# motor-shield01.net
KiCad netlist of a schematic drawn in EAGLE
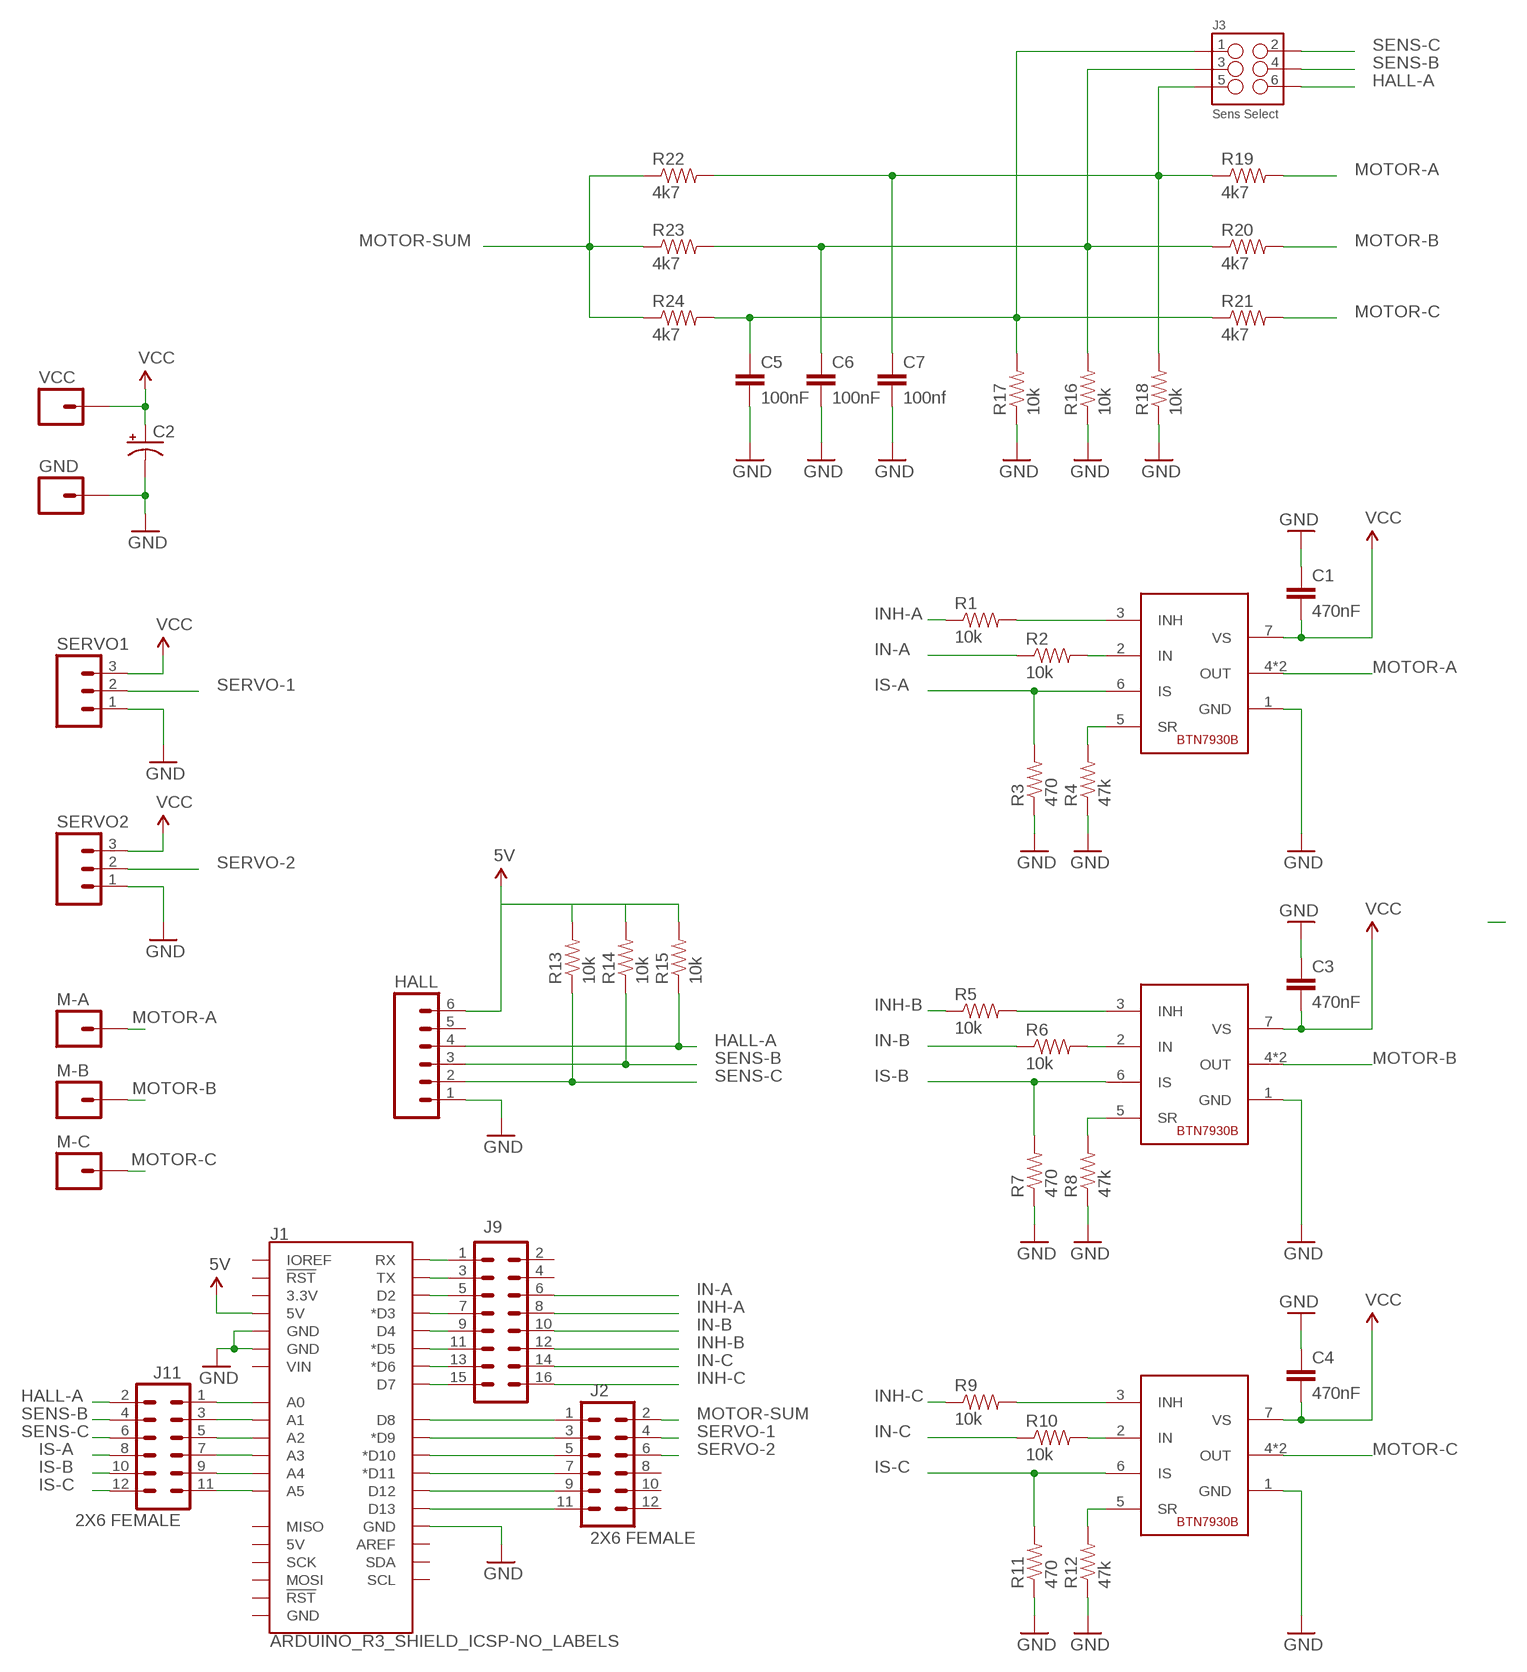
[diagram p0: schematic, sheet 1]

(export (version "E")
  (design (tool "Eeschema 10.0.6"))
  (components
    (comp (ref "C1")
      (value "470nF")
      (footprint "eagle-import:CAP-PTH-SMALLEZ")
      (libsource (lib "eagle-import") (part "CAPEZ"))
    )
    (comp (ref "C2")
      (value "CAP_POLPTH1")
      (footprint "eagle-import:CPOL-RADIAL-100UF-25V")
      (libsource (lib "eagle-import") (part "CAP_POLPTH1"))
    )
    (comp (ref "C3")
      (value "470nF")
      (footprint "eagle-import:CAP-PTH-SMALLEZ")
      (libsource (lib "eagle-import") (part "CAPEZ"))
    )
    (comp (ref "C4")
      (value "470nF")
      (footprint "eagle-import:CAP-PTH-SMALLEZ")
      (libsource (lib "eagle-import") (part "CAPEZ"))
    )
    (comp (ref "C5")
      (value "100nF")
      (footprint "eagle-import:CAP-PTH-SMALLEZ")
      (libsource (lib "eagle-import") (part "CAPEZ"))
    )
    (comp (ref "C6")
      (value "100nF")
      (footprint "eagle-import:CAP-PTH-SMALLEZ")
      (libsource (lib "eagle-import") (part "CAPEZ"))
    )
    (comp (ref "C7")
      (value "100nf")
      (footprint "eagle-import:CAP-PTH-SMALLEZ")
      (libsource (lib "eagle-import") (part "CAPEZ"))
    )
    (comp (ref "DA")
      (value "H-Bridge")
      (footprint "eagle-import:INF-PG-TO263-7-1_L_1PRIMARY")
      (libsource (lib "eagle-import") (part "INF-PG-TO263-7-1_L_1"))
    )
    (comp (ref "DB")
      (value "H-Bridge")
      (footprint "eagle-import:INF-PG-TO263-7-1_L_1PRIMARY")
      (libsource (lib "eagle-import") (part "INF-PG-TO263-7-1_L_1"))
    )
    (comp (ref "DC")
      (value "H-Bridge")
      (footprint "eagle-import:INF-PG-TO263-7-1_L_1PRIMARY")
      (libsource (lib "eagle-import") (part "INF-PG-TO263-7-1_L_1"))
    )
    (comp (ref "GND")
      (value "M01SMTRA-256-8-6")
      (footprint "eagle-import:SMTRA-256-8-6")
      (libsource (lib "eagle-import") (part "M01SMTRA-256-8-6"))
    )
    (comp (ref "HALL")
      (value "M06SMD-1MM")
      (footprint "eagle-import:1X06-1MM")
      (libsource (lib "eagle-import") (part "M06SMD-1MM"))
    )
    (comp (ref "J1")
      (value "ARDUINO_R3_SHIELD_ICSP-NO_LABELS")
      (footprint "eagle-import:UNO_R3_SHIELD_ICSP_NOLABELS")
      (libsource (lib "eagle-import") (part "ARDUINO_R3_SHIELD_ICSP-NO_LABELS"))
    )
    (comp (ref "J2")
      (value "2X6 FEMALE")
      (footprint "eagle-import:2X6")
      (libsource (lib "eagle-import") (part "M06X2PTH_FEMALE"))
    )
    (comp (ref "J3")
      (value "Sens Select")
      (footprint "eagle-import:2X3")
      (libsource (lib "eagle-import") (part "M03X2FEMALE"))
    )
    (comp (ref "J9")
      (value "M08X2")
      (footprint "eagle-import:2X8")
      (libsource (lib "eagle-import") (part "M08X2"))
    )
    (comp (ref "J11")
      (value "2X6 FEMALE")
      (footprint "eagle-import:2X6")
      (libsource (lib "eagle-import") (part "M06X2PTH_FEMALE"))
    )
    (comp (ref "M-A")
      (value "M01SMTRA-256-8-6")
      (footprint "eagle-import:SMTRA-256-8-6")
      (libsource (lib "eagle-import") (part "M01SMTRA-256-8-6"))
    )
    (comp (ref "M-B")
      (value "M01SMTRA-256-8-6")
      (footprint "eagle-import:SMTRA-256-8-6")
      (libsource (lib "eagle-import") (part "M01SMTRA-256-8-6"))
    )
    (comp (ref "M-C")
      (value "M01SMTRA-256-8-6")
      (footprint "eagle-import:SMTRA-256-8-6")
      (libsource (lib "eagle-import") (part "M01SMTRA-256-8-6"))
    )
    (comp (ref "R1")
      (value "10k")
      (footprint "eagle-import:AXIAL-0.3")
      (libsource (lib "eagle-import") (part "10KOHM-1/4W-1%(PTH)HORIZ"))
    )
    (comp (ref "R2")
      (value "10k")
      (footprint "eagle-import:AXIAL-0.3")
      (libsource (lib "eagle-import") (part "10KOHM-1/4W-1%(PTH)HORIZ"))
    )
    (comp (ref "R3")
      (value "470")
      (footprint "eagle-import:AXIAL-0.3")
      (libsource (lib "eagle-import") (part "10KOHM-1/4W-1%(PTH)HORIZ"))
    )
    (comp (ref "R4")
      (value "47k")
      (footprint "eagle-import:AXIAL-0.3")
      (libsource (lib "eagle-import") (part "10KOHM-1/4W-1%(PTH)HORIZ"))
    )
    (comp (ref "R5")
      (value "10k")
      (footprint "eagle-import:AXIAL-0.3")
      (libsource (lib "eagle-import") (part "10KOHM-1/4W-1%(PTH)HORIZ"))
    )
    (comp (ref "R6")
      (value "10k")
      (footprint "eagle-import:AXIAL-0.3")
      (libsource (lib "eagle-import") (part "10KOHM-1/4W-1%(PTH)HORIZ"))
    )
    (comp (ref "R7")
      (value "470")
      (footprint "eagle-import:AXIAL-0.3")
      (libsource (lib "eagle-import") (part "10KOHM-1/4W-1%(PTH)HORIZ"))
    )
    (comp (ref "R8")
      (value "47k")
      (footprint "eagle-import:AXIAL-0.3")
      (libsource (lib "eagle-import") (part "10KOHM-1/4W-1%(PTH)HORIZ"))
    )
    (comp (ref "R9")
      (value "10k")
      (footprint "eagle-import:AXIAL-0.3")
      (libsource (lib "eagle-import") (part "10KOHM-1/4W-1%(PTH)HORIZ"))
    )
    (comp (ref "R10")
      (value "10k")
      (footprint "eagle-import:AXIAL-0.3")
      (libsource (lib "eagle-import") (part "10KOHM-1/4W-1%(PTH)HORIZ"))
    )
    (comp (ref "R11")
      (value "470")
      (footprint "eagle-import:AXIAL-0.3")
      (libsource (lib "eagle-import") (part "10KOHM-1/4W-1%(PTH)HORIZ"))
    )
    (comp (ref "R12")
      (value "47k")
      (footprint "eagle-import:AXIAL-0.3")
      (libsource (lib "eagle-import") (part "10KOHM-1/4W-1%(PTH)HORIZ"))
    )
    (comp (ref "R13")
      (value "10k")
      (footprint "eagle-import:AXIAL-0.3")
      (libsource (lib "eagle-import") (part "10KOHM-1/4W-1%(PTH)HORIZ"))
    )
    (comp (ref "R14")
      (value "10k")
      (footprint "eagle-import:AXIAL-0.3")
      (libsource (lib "eagle-import") (part "10KOHM-1/4W-1%(PTH)HORIZ"))
    )
    (comp (ref "R15")
      (value "10k")
      (footprint "eagle-import:AXIAL-0.3")
      (libsource (lib "eagle-import") (part "10KOHM-1/4W-1%(PTH)HORIZ"))
    )
    (comp (ref "R16")
      (value "10k")
      (footprint "eagle-import:AXIAL-0.3")
      (libsource (lib "eagle-import") (part "10KOHM-1/4W-1%(PTH)HORIZ"))
    )
    (comp (ref "R17")
      (value "10k")
      (footprint "eagle-import:AXIAL-0.3")
      (libsource (lib "eagle-import") (part "10KOHM-1/4W-1%(PTH)HORIZ"))
    )
    (comp (ref "R18")
      (value "10k")
      (footprint "eagle-import:AXIAL-0.3")
      (libsource (lib "eagle-import") (part "10KOHM-1/4W-1%(PTH)HORIZ"))
    )
    (comp (ref "R19")
      (value "4k7")
      (footprint "eagle-import:AXIAL-0.3")
      (libsource (lib "eagle-import") (part "10KOHM-1/4W-1%(PTH)HORIZ"))
    )
    (comp (ref "R20")
      (value "4k7")
      (footprint "eagle-import:AXIAL-0.3")
      (libsource (lib "eagle-import") (part "10KOHM-1/4W-1%(PTH)HORIZ"))
    )
    (comp (ref "R21")
      (value "4k7")
      (footprint "eagle-import:AXIAL-0.3")
      (libsource (lib "eagle-import") (part "10KOHM-1/4W-1%(PTH)HORIZ"))
    )
    (comp (ref "R22")
      (value "4k7")
      (footprint "eagle-import:AXIAL-0.3")
      (libsource (lib "eagle-import") (part "10KOHM-1/4W-1%(PTH)HORIZ"))
    )
    (comp (ref "R23")
      (value "4k7")
      (footprint "eagle-import:AXIAL-0.3")
      (libsource (lib "eagle-import") (part "10KOHM-1/4W-1%(PTH)HORIZ"))
    )
    (comp (ref "R24")
      (value "4k7")
      (footprint "eagle-import:AXIAL-0.3")
      (libsource (lib "eagle-import") (part "10KOHM-1/4W-1%(PTH)HORIZ"))
    )
    (comp (ref "SERVO1")
      (value "M03PTH")
      (footprint "eagle-import:1X03")
      (libsource (lib "eagle-import") (part "M03PTH"))
    )
    (comp (ref "SERVO2")
      (value "M03PTH")
      (footprint "eagle-import:1X03")
      (libsource (lib "eagle-import") (part "M03PTH"))
    )
    (comp (ref "VCC")
      (value "M01SMTRA-256-8-6")
      (footprint "eagle-import:SMTRA-256-8-6")
      (libsource (lib "eagle-import") (part "M01SMTRA-256-8-6"))
    )
  )
  (nets
    (net (code "1") (name "/HALL-A") (class "Default")
      (node (ref "HALL") (pin "4") (pinfunction "4_4") (pintype "passive"))
      (node (ref "J11") (pin "2") (pinfunction "2_2") (pintype "passive"))
      (node (ref "J3") (pin "6") (pinfunction "6_6") (pintype "bidirectional"))
      (node (ref "R15") (pin "P$1") (pinfunction "1_P$1") (pintype "passive"))
    )
    (net (code "2") (name "/IN-A") (class "Default")
      (node (ref "J9") (pin "6") (pinfunction "6_6") (pintype "passive"))
      (node (ref "R2") (pin "P$1") (pinfunction "1_P$1") (pintype "passive"))
    )
    (net (code "3") (name "/IN-B") (class "Default")
      (node (ref "J9") (pin "10") (pinfunction "10_10") (pintype "passive"))
      (node (ref "R6") (pin "P$1") (pinfunction "1_P$1") (pintype "passive"))
    )
    (net (code "4") (name "/IN-C") (class "Default")
      (node (ref "J9") (pin "14") (pinfunction "14_14") (pintype "passive"))
      (node (ref "R10") (pin "P$1") (pinfunction "1_P$1") (pintype "passive"))
    )
    (net (code "5") (name "/INH-A") (class "Default")
      (node (ref "J9") (pin "8") (pinfunction "8_8") (pintype "passive"))
      (node (ref "R1") (pin "P$1") (pinfunction "1_P$1") (pintype "passive"))
    )
    (net (code "6") (name "/INH-B") (class "Default")
      (node (ref "J9") (pin "12") (pinfunction "12_12") (pintype "passive"))
      (node (ref "R5") (pin "P$1") (pinfunction "1_P$1") (pintype "passive"))
    )
    (net (code "7") (name "/INH-C") (class "Default")
      (node (ref "J9") (pin "16") (pinfunction "16_16") (pintype "passive"))
      (node (ref "R9") (pin "P$1") (pinfunction "1_P$1") (pintype "passive"))
    )
    (net (code "8") (name "/IS-A") (class "Default")
      (node (ref "DA") (pin "6") (pinfunction "IS_6") (pintype "bidirectional"))
      (node (ref "J11") (pin "8") (pinfunction "8_8") (pintype "passive"))
      (node (ref "R3") (pin "P$2") (pinfunction "2_P$2") (pintype "passive"))
    )
    (net (code "9") (name "/IS-B") (class "Default")
      (node (ref "DB") (pin "6") (pinfunction "IS_6") (pintype "bidirectional"))
      (node (ref "J11") (pin "10") (pinfunction "10_10") (pintype "passive"))
      (node (ref "R7") (pin "P$2") (pinfunction "2_P$2") (pintype "passive"))
    )
    (net (code "10") (name "/IS-C") (class "Default")
      (node (ref "DC") (pin "6") (pinfunction "IS_6") (pintype "bidirectional"))
      (node (ref "J11") (pin "12") (pinfunction "12_12") (pintype "passive"))
      (node (ref "R11") (pin "P$2") (pinfunction "2_P$2") (pintype "passive"))
    )
    (net (code "11") (name "/MOTOR-A") (class "Default")
      (node (ref "DA") (pin "4") (pinfunction "OUT_4") (pintype "bidirectional"))
      (node (ref "DA") (pin "8") (pinfunction "OUT_8") (pintype "bidirectional"))
      (node (ref "M-A") (pin "P$1") (pinfunction "1_P$1") (pintype "passive"))
      (node (ref "R19") (pin "P$2") (pinfunction "2_P$2") (pintype "passive"))
    )
    (net (code "12") (name "/MOTOR-B") (class "Default")
      (node (ref "DB") (pin "4") (pinfunction "OUT_4") (pintype "bidirectional"))
      (node (ref "DB") (pin "8") (pinfunction "OUT_8") (pintype "bidirectional"))
      (node (ref "M-B") (pin "P$1") (pinfunction "1_P$1") (pintype "passive"))
      (node (ref "R20") (pin "P$2") (pinfunction "2_P$2") (pintype "passive"))
    )
    (net (code "13") (name "/MOTOR-C") (class "Default")
      (node (ref "DC") (pin "4") (pinfunction "OUT_4") (pintype "bidirectional"))
      (node (ref "DC") (pin "8") (pinfunction "OUT_8") (pintype "bidirectional"))
      (node (ref "M-C") (pin "P$1") (pinfunction "1_P$1") (pintype "passive"))
      (node (ref "R21") (pin "P$2") (pinfunction "2_P$2") (pintype "passive"))
    )
    (net (code "14") (name "/MOTOR-SUM") (class "Default")
      (node (ref "J2") (pin "2") (pinfunction "2_2") (pintype "passive"))
      (node (ref "R22") (pin "P$1") (pinfunction "1_P$1") (pintype "passive"))
      (node (ref "R23") (pin "P$1") (pinfunction "1_P$1") (pintype "passive"))
      (node (ref "R24") (pin "P$1") (pinfunction "1_P$1") (pintype "passive"))
    )
    (net (code "15") (name "/N$2") (class "Default")
      (node (ref "DA") (pin "2") (pinfunction "IN_2") (pintype "bidirectional"))
      (node (ref "R2") (pin "P$2") (pinfunction "2_P$2") (pintype "passive"))
    )
    (net (code "16") (name "/SENS-B") (class "Default")
      (node (ref "HALL") (pin "3") (pinfunction "3_3") (pintype "passive"))
      (node (ref "J11") (pin "4") (pinfunction "4_4") (pintype "passive"))
      (node (ref "J3") (pin "4") (pinfunction "4_4") (pintype "bidirectional"))
      (node (ref "R14") (pin "P$1") (pinfunction "1_P$1") (pintype "passive"))
    )
    (net (code "17") (name "/SENS-C") (class "Default")
      (node (ref "HALL") (pin "2") (pinfunction "2_2") (pintype "passive"))
      (node (ref "J11") (pin "6") (pinfunction "6_6") (pintype "passive"))
      (node (ref "J3") (pin "2") (pinfunction "2_2") (pintype "bidirectional"))
      (node (ref "R13") (pin "P$1") (pinfunction "1_P$1") (pintype "passive"))
    )
    (net (code "18") (name "/SERVO-1") (class "Default")
      (node (ref "J2") (pin "4") (pinfunction "4_4") (pintype "passive"))
      (node (ref "SERVO1") (pin "2") (pinfunction "2_2") (pintype "passive"))
    )
    (net (code "19") (name "/SERVO-2") (class "Default")
      (node (ref "J2") (pin "6") (pinfunction "6_6") (pintype "passive"))
      (node (ref "SERVO2") (pin "2") (pinfunction "2_2") (pintype "passive"))
    )
    (net (code "20") (name "5V") (class "Default")
      (node (ref "HALL") (pin "6") (pinfunction "6_6") (pintype "passive"))
      (node (ref "J1") (pin "5V") (pinfunction "5V_5V") (pintype "bidirectional"))
      (node (ref "R13") (pin "P$2") (pinfunction "2_P$2") (pintype "passive"))
      (node (ref "R14") (pin "P$2") (pinfunction "2_P$2") (pintype "passive"))
      (node (ref "R15") (pin "P$2") (pinfunction "2_P$2") (pintype "passive"))
    )
    (net (code "21") (name "GND") (class "Default")
      (node (ref "C1") (pin "1") (pinfunction "1_1") (pintype "passive"))
      (node (ref "C2") (pin "2") (pinfunction "-_2") (pintype "passive"))
      (node (ref "C3") (pin "1") (pinfunction "1_1") (pintype "passive"))
      (node (ref "C4") (pin "1") (pinfunction "1_1") (pintype "passive"))
      (node (ref "C5") (pin "2") (pinfunction "2_2") (pintype "passive"))
      (node (ref "C6") (pin "2") (pinfunction "2_2") (pintype "passive"))
      (node (ref "C7") (pin "2") (pinfunction "2_2") (pintype "passive"))
      (node (ref "DA") (pin "1") (pinfunction "GND_1") (pintype "bidirectional"))
      (node (ref "DB") (pin "1") (pinfunction "GND_1") (pintype "bidirectional"))
      (node (ref "DC") (pin "1") (pinfunction "GND_1") (pintype "bidirectional"))
      (node (ref "GND") (pin "P$1") (pinfunction "1_P$1") (pintype "passive"))
      (node (ref "HALL") (pin "1") (pinfunction "1_1") (pintype "passive"))
      (node (ref "J1") (pin "GND@0") (pinfunction "GND_GND@0") (pintype "bidirectional"))
      (node (ref "J1") (pin "GND@1") (pinfunction "GND_GND@1") (pintype "bidirectional"))
      (node (ref "J1") (pin "GND@2") (pinfunction "GND_GND@2") (pintype "bidirectional"))
      (node (ref "R11") (pin "P$1") (pinfunction "1_P$1") (pintype "passive"))
      (node (ref "R12") (pin "P$1") (pinfunction "1_P$1") (pintype "passive"))
      (node (ref "R16") (pin "P$1") (pinfunction "1_P$1") (pintype "passive"))
      (node (ref "R17") (pin "P$1") (pinfunction "1_P$1") (pintype "passive"))
      (node (ref "R18") (pin "P$1") (pinfunction "1_P$1") (pintype "passive"))
      (node (ref "R3") (pin "P$1") (pinfunction "1_P$1") (pintype "passive"))
      (node (ref "R4") (pin "P$1") (pinfunction "1_P$1") (pintype "passive"))
      (node (ref "R7") (pin "P$1") (pinfunction "1_P$1") (pintype "passive"))
      (node (ref "R8") (pin "P$1") (pinfunction "1_P$1") (pintype "passive"))
      (node (ref "SERVO1") (pin "1") (pinfunction "1_1") (pintype "passive"))
      (node (ref "SERVO2") (pin "1") (pinfunction "1_1") (pintype "passive"))
    )
    (net (code "22") (name "Net-(DA-INH)") (class "Default")
      (node (ref "DA") (pin "3") (pinfunction "INH_3") (pintype "bidirectional"))
      (node (ref "R1") (pin "P$2") (pinfunction "2_P$2") (pintype "passive"))
    )
    (net (code "23") (name "Net-(DA-SR)") (class "Default")
      (node (ref "DA") (pin "5") (pinfunction "SR_5") (pintype "bidirectional"))
      (node (ref "R4") (pin "P$2") (pinfunction "2_P$2") (pintype "passive"))
    )
    (net (code "24") (name "Net-(DB-IN)") (class "Default")
      (node (ref "DB") (pin "2") (pinfunction "IN_2") (pintype "bidirectional"))
      (node (ref "R6") (pin "P$2") (pinfunction "2_P$2") (pintype "passive"))
    )
    (net (code "25") (name "Net-(DB-INH)") (class "Default")
      (node (ref "DB") (pin "3") (pinfunction "INH_3") (pintype "bidirectional"))
      (node (ref "R5") (pin "P$2") (pinfunction "2_P$2") (pintype "passive"))
    )
    (net (code "26") (name "Net-(DB-SR)") (class "Default")
      (node (ref "DB") (pin "5") (pinfunction "SR_5") (pintype "bidirectional"))
      (node (ref "R8") (pin "P$2") (pinfunction "2_P$2") (pintype "passive"))
    )
    (net (code "27") (name "Net-(DC-IN)") (class "Default")
      (node (ref "DC") (pin "2") (pinfunction "IN_2") (pintype "bidirectional"))
      (node (ref "R10") (pin "P$2") (pinfunction "2_P$2") (pintype "passive"))
    )
    (net (code "28") (name "Net-(DC-INH)") (class "Default")
      (node (ref "DC") (pin "3") (pinfunction "INH_3") (pintype "bidirectional"))
      (node (ref "R9") (pin "P$2") (pinfunction "2_P$2") (pintype "passive"))
    )
    (net (code "29") (name "Net-(DC-SR)") (class "Default")
      (node (ref "DC") (pin "5") (pinfunction "SR_5") (pintype "bidirectional"))
      (node (ref "R12") (pin "P$2") (pinfunction "2_P$2") (pintype "passive"))
    )
    (net (code "30") (name "Net-(J1-*D3)") (class "Default")
      (node (ref "J1") (pin "D3") (pinfunction "*D3_D3") (pintype "bidirectional"))
      (node (ref "J9") (pin "7") (pinfunction "7_7") (pintype "passive"))
    )
    (net (code "31") (name "Net-(J1-*D5)") (class "Default")
      (node (ref "J1") (pin "D5") (pinfunction "*D5_D5") (pintype "bidirectional"))
      (node (ref "J9") (pin "11") (pinfunction "11_11") (pintype "passive"))
    )
    (net (code "32") (name "Net-(J1-*D6)") (class "Default")
      (node (ref "J1") (pin "D6") (pinfunction "*D6_D6") (pintype "bidirectional"))
      (node (ref "J9") (pin "13") (pinfunction "13_13") (pintype "passive"))
    )
    (net (code "33") (name "Net-(J1-*D9)") (class "Default")
      (node (ref "J1") (pin "D9") (pinfunction "*D9_D9") (pintype "bidirectional"))
      (node (ref "J2") (pin "3") (pinfunction "3_3") (pintype "passive"))
    )
    (net (code "34") (name "Net-(J1-*D10)") (class "Default")
      (node (ref "J1") (pin "D10") (pinfunction "*D10_D10") (pintype "bidirectional"))
      (node (ref "J2") (pin "5") (pinfunction "5_5") (pintype "passive"))
    )
    (net (code "35") (name "Net-(J1-*D11)") (class "Default")
      (node (ref "J1") (pin "D11") (pinfunction "*D11_D11") (pintype "bidirectional"))
      (node (ref "J2") (pin "7") (pinfunction "7_7") (pintype "passive"))
    )
    (net (code "36") (name "Net-(J1-PadA0)") (class "Default")
      (node (ref "J1") (pin "A0") (pinfunction "A0_A0") (pintype "bidirectional"))
      (node (ref "J11") (pin "1") (pinfunction "1_1") (pintype "passive"))
    )
    (net (code "37") (name "Net-(J1-PadA1)") (class "Default")
      (node (ref "J1") (pin "A1") (pinfunction "A1_A1") (pintype "bidirectional"))
      (node (ref "J11") (pin "3") (pinfunction "3_3") (pintype "passive"))
    )
    (net (code "38") (name "Net-(J1-PadA2)") (class "Default")
      (node (ref "J1") (pin "A2") (pinfunction "A2_A2") (pintype "bidirectional"))
      (node (ref "J11") (pin "5") (pinfunction "5_5") (pintype "passive"))
    )
    (net (code "39") (name "Net-(J1-PadA3)") (class "Default")
      (node (ref "J1") (pin "A3") (pinfunction "A3_A3") (pintype "bidirectional"))
      (node (ref "J11") (pin "7") (pinfunction "7_7") (pintype "passive"))
    )
    (net (code "40") (name "Net-(J1-PadA4)") (class "Default")
      (node (ref "J1") (pin "A4") (pinfunction "A4_A4") (pintype "bidirectional"))
      (node (ref "J11") (pin "9") (pinfunction "9_9") (pintype "passive"))
    )
    (net (code "41") (name "Net-(J1-PadA5)") (class "Default")
      (node (ref "J1") (pin "A5") (pinfunction "A5_A5") (pintype "bidirectional"))
      (node (ref "J11") (pin "11") (pinfunction "11_11") (pintype "passive"))
    )
    (net (code "42") (name "Net-(J1-PadD2)") (class "Default")
      (node (ref "J1") (pin "D2") (pinfunction "D2_D2") (pintype "bidirectional"))
      (node (ref "J9") (pin "5") (pinfunction "5_5") (pintype "passive"))
    )
    (net (code "43") (name "Net-(J1-PadD4)") (class "Default")
      (node (ref "J1") (pin "D4") (pinfunction "D4_D4") (pintype "bidirectional"))
      (node (ref "J9") (pin "9") (pinfunction "9_9") (pintype "passive"))
    )
    (net (code "44") (name "Net-(J1-PadD7)") (class "Default")
      (node (ref "J1") (pin "D7") (pinfunction "D7_D7") (pintype "bidirectional"))
      (node (ref "J9") (pin "15") (pinfunction "15_15") (pintype "passive"))
    )
    (net (code "45") (name "Net-(J1-PadD8)") (class "Default")
      (node (ref "J1") (pin "D8") (pinfunction "D8_D8") (pintype "bidirectional"))
      (node (ref "J2") (pin "1") (pinfunction "1_1") (pintype "passive"))
    )
    (net (code "46") (name "Net-(J1-PadD12)") (class "Default")
      (node (ref "J1") (pin "D12") (pinfunction "D12_D12") (pintype "bidirectional"))
      (node (ref "J2") (pin "9") (pinfunction "9_9") (pintype "passive"))
    )
    (net (code "47") (name "Net-(J1-PadD13)") (class "Default")
      (node (ref "J1") (pin "D13") (pinfunction "D13_D13") (pintype "bidirectional"))
      (node (ref "J2") (pin "11") (pinfunction "11_11") (pintype "passive"))
    )
    (net (code "48") (name "Net-(J1-PadRX)") (class "Default")
      (node (ref "J1") (pin "RX") (pinfunction "RX_RX") (pintype "bidirectional"))
      (node (ref "J9") (pin "1") (pinfunction "1_1") (pintype "passive"))
    )
    (net (code "49") (name "Net-(J1-PadTX)") (class "Default")
      (node (ref "J1") (pin "TX") (pinfunction "TX_TX") (pintype "bidirectional"))
      (node (ref "J9") (pin "3") (pinfunction "3_3") (pintype "passive"))
    )
    (net (code "50") (name "Net-(R16-2)") (class "Default")
      (node (ref "C6") (pin "1") (pinfunction "1_1") (pintype "passive"))
      (node (ref "J3") (pin "3") (pinfunction "3_3") (pintype "bidirectional"))
      (node (ref "R16") (pin "P$2") (pinfunction "2_P$2") (pintype "passive"))
      (node (ref "R20") (pin "P$1") (pinfunction "1_P$1") (pintype "passive"))
      (node (ref "R23") (pin "P$2") (pinfunction "2_P$2") (pintype "passive"))
    )
    (net (code "51") (name "Net-(R17-2)") (class "Default")
      (node (ref "C5") (pin "1") (pinfunction "1_1") (pintype "passive"))
      (node (ref "J3") (pin "1") (pinfunction "1_1") (pintype "bidirectional"))
      (node (ref "R17") (pin "P$2") (pinfunction "2_P$2") (pintype "passive"))
      (node (ref "R21") (pin "P$1") (pinfunction "1_P$1") (pintype "passive"))
      (node (ref "R24") (pin "P$2") (pinfunction "2_P$2") (pintype "passive"))
    )
    (net (code "52") (name "Net-(R18-2)") (class "Default")
      (node (ref "C7") (pin "1") (pinfunction "1_1") (pintype "passive"))
      (node (ref "J3") (pin "5") (pinfunction "5_5") (pintype "bidirectional"))
      (node (ref "R18") (pin "P$2") (pinfunction "2_P$2") (pintype "passive"))
      (node (ref "R19") (pin "P$1") (pinfunction "1_P$1") (pintype "passive"))
      (node (ref "R22") (pin "P$2") (pinfunction "2_P$2") (pintype "passive"))
    )
    (net (code "53") (name "VCC") (class "Default")
      (node (ref "C1") (pin "2") (pinfunction "2_2") (pintype "passive"))
      (node (ref "C2") (pin "1") (pinfunction "+_1") (pintype "passive"))
      (node (ref "C3") (pin "2") (pinfunction "2_2") (pintype "passive"))
      (node (ref "C4") (pin "2") (pinfunction "2_2") (pintype "passive"))
      (node (ref "DA") (pin "7") (pinfunction "VS_7") (pintype "bidirectional"))
      (node (ref "DB") (pin "7") (pinfunction "VS_7") (pintype "bidirectional"))
      (node (ref "DC") (pin "7") (pinfunction "VS_7") (pintype "bidirectional"))
      (node (ref "SERVO1") (pin "3") (pinfunction "3_3") (pintype "passive"))
      (node (ref "SERVO2") (pin "3") (pinfunction "3_3") (pintype "passive"))
      (node (ref "VCC") (pin "P$1") (pinfunction "1_P$1") (pintype "passive"))
    )
    (net (code "54") (name "unconnected-(HALL-Pad5)") (class "Default")
      (node (ref "HALL") (pin "5") (pinfunction "5_5") (pintype "passive"))
    )
    (net (code "55") (name "unconnected-(J1-5V-Pad5V_ICSP)") (class "Default")
      (node (ref "J1") (pin "5V_ICSP") (pinfunction "5V_5V_ICSP") (pintype "bidirectional"))
    )
    (net (code "56") (name "unconnected-(J1-GND-PadGND_ICSP)") (class "Default")
      (node (ref "J1") (pin "GND_ICSP") (pinfunction "GND_GND_ICSP") (pintype "bidirectional"))
    )
    (net (code "57") (name "unconnected-(J1-Pad3.3V)") (class "Default")
      (node (ref "J1") (pin "3.3V") (pinfunction "3.3V_3.3V") (pintype "bidirectional"))
    )
    (net (code "58") (name "unconnected-(J1-PadAREF)") (class "Default")
      (node (ref "J1") (pin "AREF") (pinfunction "AREF_AREF") (pintype "bidirectional"))
    )
    (net (code "59") (name "unconnected-(J1-PadIOREF)") (class "Default")
      (node (ref "J1") (pin "IOREF") (pinfunction "IOREF_IOREF") (pintype "bidirectional"))
    )
    (net (code "60") (name "unconnected-(J1-PadMISO)") (class "Default")
      (node (ref "J1") (pin "MISO") (pinfunction "MISO_MISO") (pintype "bidirectional"))
    )
    (net (code "61") (name "unconnected-(J1-PadMOSI)") (class "Default")
      (node (ref "J1") (pin "MOSI") (pinfunction "MOSI_MOSI") (pintype "bidirectional"))
    )
    (net (code "62") (name "unconnected-(J1-PadSCK)") (class "Default")
      (node (ref "J1") (pin "SCK") (pinfunction "SCK_SCK") (pintype "bidirectional"))
    )
    (net (code "63") (name "unconnected-(J1-PadSCL)") (class "Default")
      (node (ref "J1") (pin "SCL") (pinfunction "SCL_SCL") (pintype "bidirectional"))
    )
    (net (code "64") (name "unconnected-(J1-PadSDA)") (class "Default")
      (node (ref "J1") (pin "SDA") (pinfunction "SDA_SDA") (pintype "bidirectional"))
    )
    (net (code "65") (name "unconnected-(J1-PadVIN)") (class "Default")
      (node (ref "J1") (pin "VIN") (pinfunction "VIN_VIN") (pintype "bidirectional"))
    )
    (net (code "66") (name "unconnected-(J1-~{RST}-PadRES)") (class "Default")
      (node (ref "J1") (pin "RES") (pinfunction "~{RST}_RES") (pintype "bidirectional"))
    )
    (net (code "67") (name "unconnected-(J1-~{RST}-PadRST_ICSP)") (class "Default")
      (node (ref "J1") (pin "RST_ICSP") (pinfunction "~{RST}_RST_ICSP") (pintype "bidirectional"))
    )
    (net (code "68") (name "unconnected-(J2-Pad8)") (class "Default")
      (node (ref "J2") (pin "8") (pinfunction "8_8") (pintype "passive"))
    )
    (net (code "69") (name "unconnected-(J2-Pad10)") (class "Default")
      (node (ref "J2") (pin "10") (pinfunction "10_10") (pintype "passive"))
    )
    (net (code "70") (name "unconnected-(J2-Pad12)") (class "Default")
      (node (ref "J2") (pin "12") (pinfunction "12_12") (pintype "passive"))
    )
    (net (code "71") (name "unconnected-(J9-Pad2)") (class "Default")
      (node (ref "J9") (pin "2") (pinfunction "2_2") (pintype "passive"))
    )
    (net (code "72") (name "unconnected-(J9-Pad4)") (class "Default")
      (node (ref "J9") (pin "4") (pinfunction "4_4") (pintype "passive"))
    )
  )
)
